# ABS_ENC_IF.net
KiCad netlist of a schematic drawn in Altium Designer
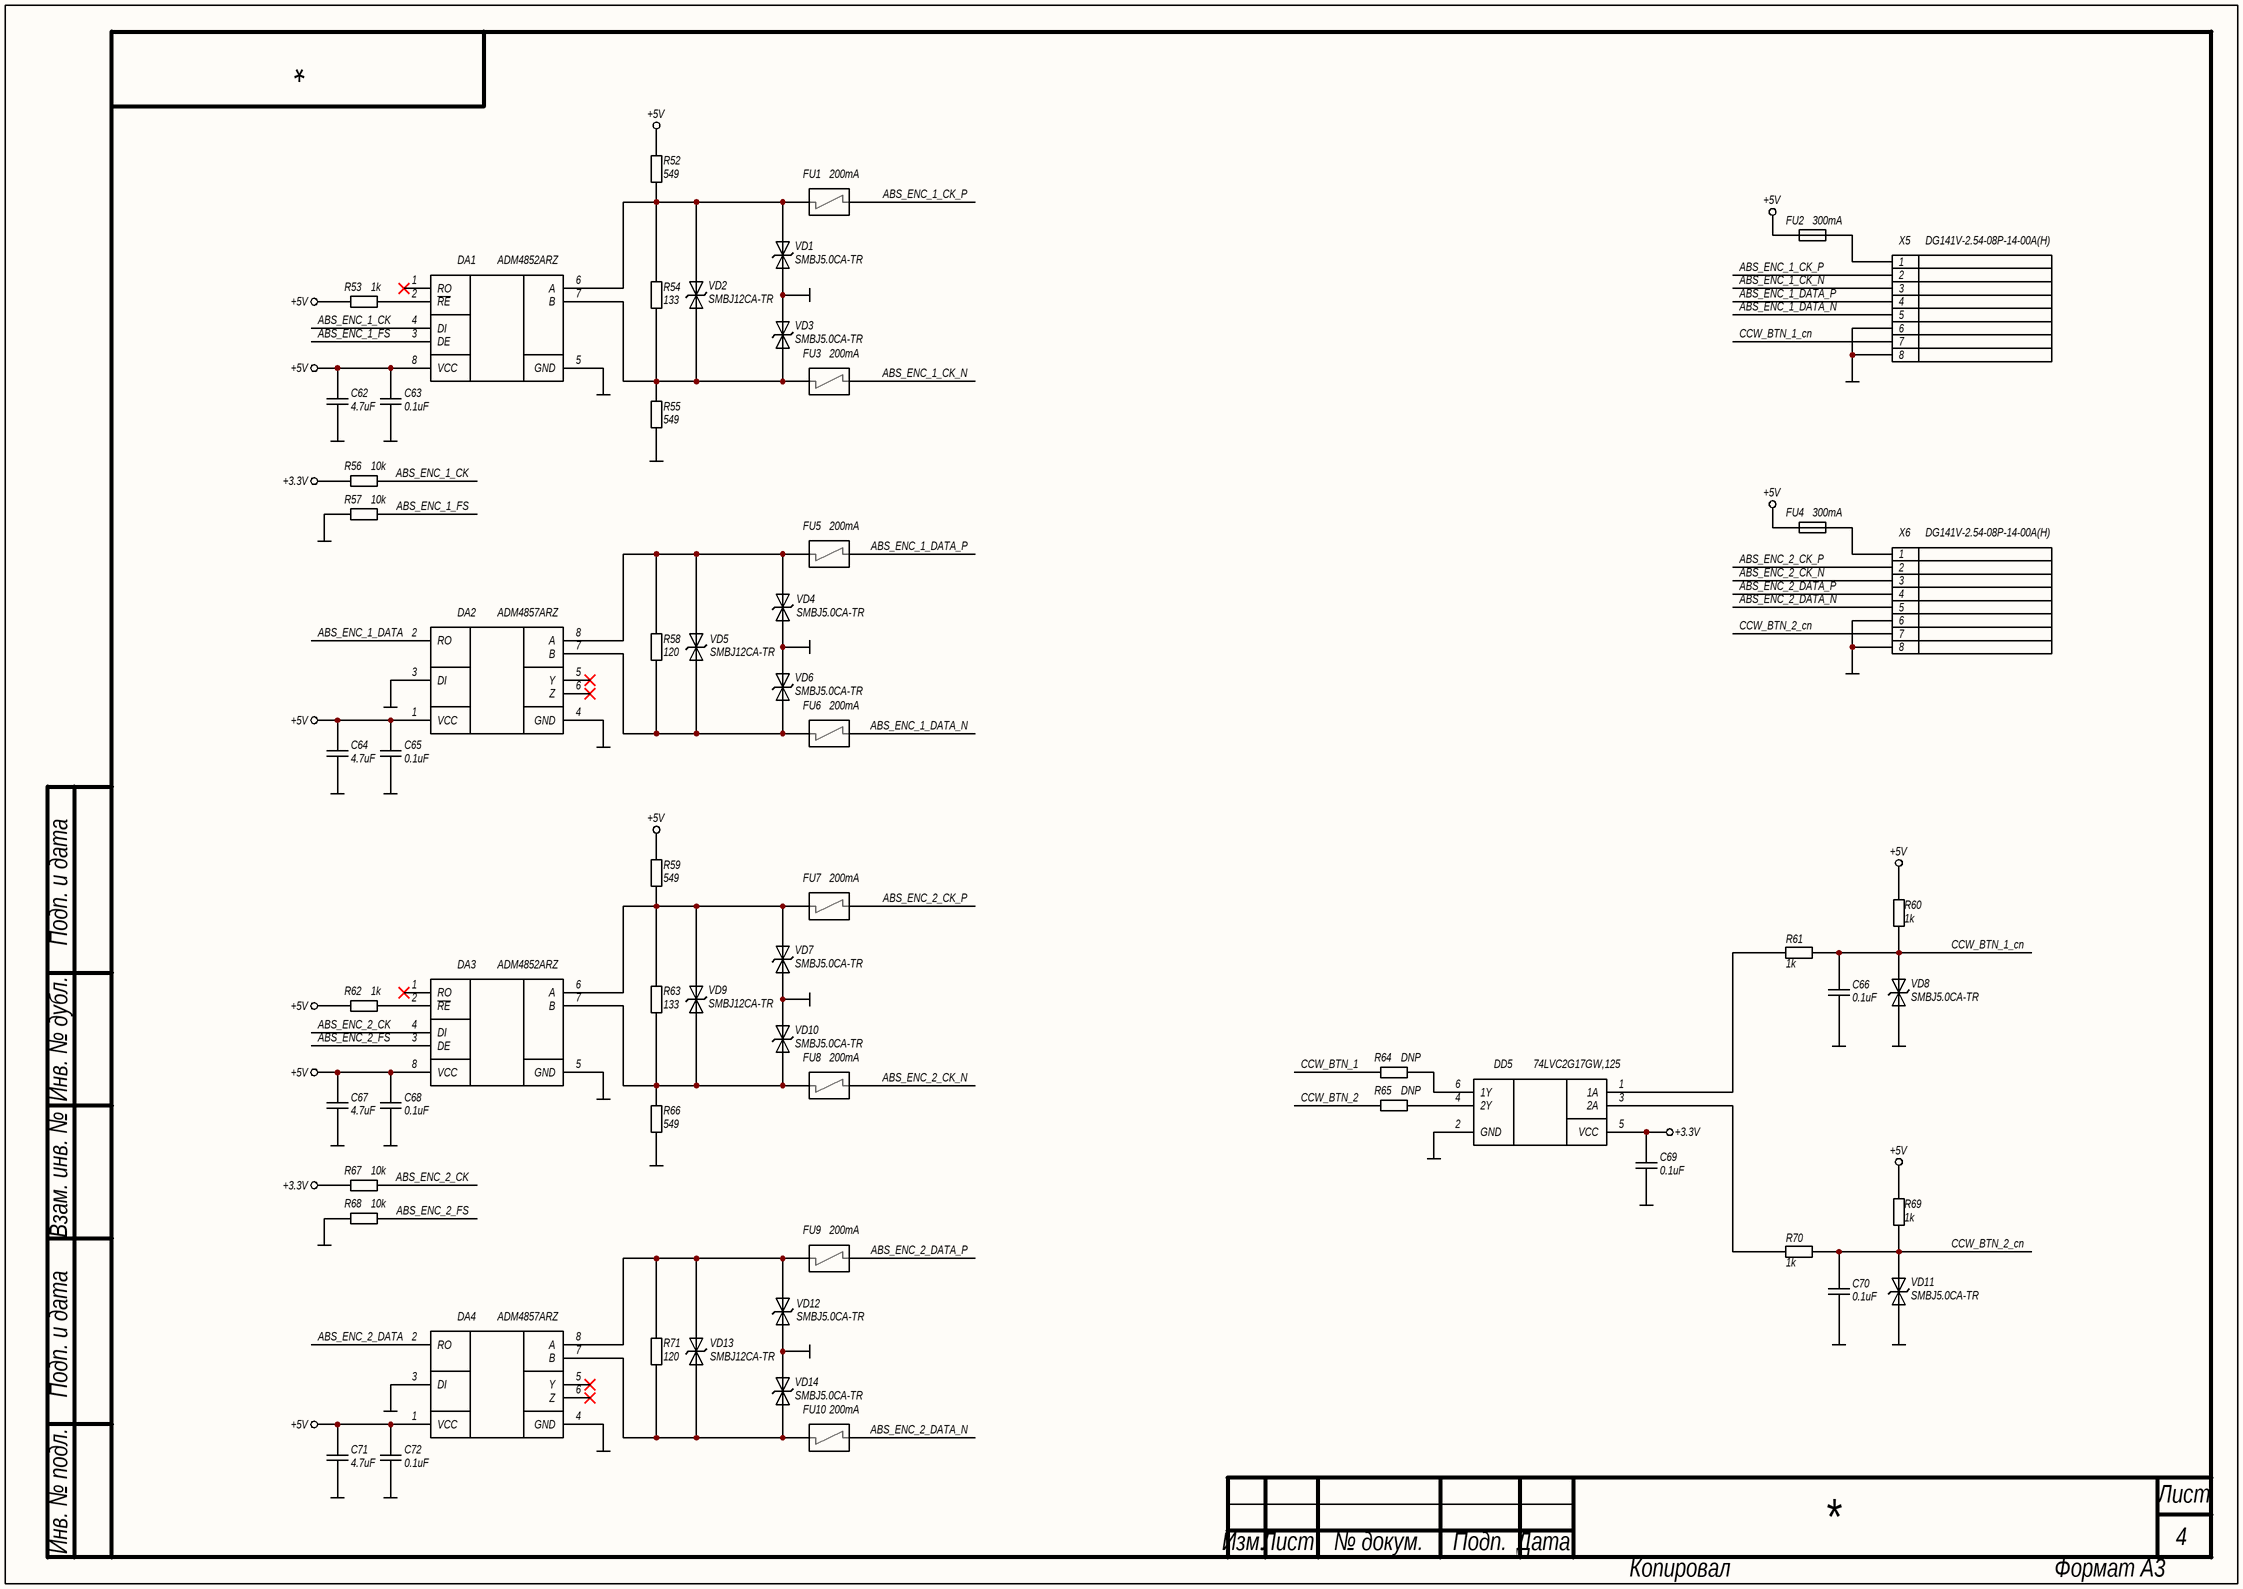
[diagram p0: ABS_ENC_IF.SchDoc]

(export (version "E")
  (design (tool "Eeschema 10.0.6"))
  (components
    (comp (ref "C62")
      (value "4.7uF")
      (footprint "C0603N")
      (description "Конденсатор")
      (libsource (lib "Components Library") (part "CAP_FIXED"))
    )
    (comp (ref "C63")
      (value "0.1uF")
      (footprint "C0603N")
      (description "Конденсатор")
      (libsource (lib "Components Library") (part "CAP_FIXED"))
    )
    (comp (ref "C64")
      (value "4.7uF")
      (footprint "C0603N")
      (description "Конденсатор")
      (libsource (lib "Components Library") (part "CAP_FIXED"))
    )
    (comp (ref "C65")
      (value "0.1uF")
      (footprint "C0603N")
      (description "Конденсатор")
      (libsource (lib "Components Library") (part "CAP_FIXED"))
    )
    (comp (ref "C66")
      (value "0.1uF")
      (footprint "C0603N")
      (description "Конденсатор")
      (libsource (lib "Components Library") (part "CAP_FIXED"))
    )
    (comp (ref "C67")
      (value "4.7uF")
      (footprint "C0603N")
      (description "Конденсатор")
      (libsource (lib "Components Library") (part "CAP_FIXED"))
    )
    (comp (ref "C68")
      (value "0.1uF")
      (footprint "C0603N")
      (description "Конденсатор")
      (libsource (lib "Components Library") (part "CAP_FIXED"))
    )
    (comp (ref "C69")
      (value "0.1uF")
      (footprint "C0603N")
      (description "Конденсатор")
      (libsource (lib "Components Library") (part "CAP_FIXED"))
    )
    (comp (ref "C70")
      (value "0.1uF")
      (footprint "C0603N")
      (description "Конденсатор")
      (libsource (lib "Components Library") (part "CAP_FIXED"))
    )
    (comp (ref "C71")
      (value "4.7uF")
      (footprint "C0603N")
      (description "Конденсатор")
      (libsource (lib "Components Library") (part "CAP_FIXED"))
    )
    (comp (ref "C72")
      (value "0.1uF")
      (footprint "C0603N")
      (description "Конденсатор")
      (libsource (lib "Components Library") (part "CAP_FIXED"))
    )
    (comp (ref "DA1")
      (value "ADM4852ARZ")
      (footprint "SOIC8")
      (description "Микросхема интерфейса RS485")
      (libsource (lib "Components Library") (part "ADM4852A"))
    )
    (comp (ref "DA2")
      (value "ADM4857ARZ")
      (footprint "SOIC8")
      (description "Микросхема интерфейса RS485")
      (libsource (lib "Components Library") (part "ADM4857A"))
    )
    (comp (ref "DA3")
      (value "ADM4852ARZ")
      (footprint "SOIC8")
      (description "Микросхема интерфейса RS485")
      (libsource (lib "Components Library") (part "ADM4852A"))
    )
    (comp (ref "DA4")
      (value "ADM4857ARZ")
      (footprint "SOIC8")
      (description "Микросхема интерфейса RS485")
      (libsource (lib "Components Library") (part "ADM4857A"))
    )
    (comp (ref "DD5")
      (value "74LVC2G17GW,125")
      (footprint "SOT363-2")
      (description "Микросхема сдвоенный триггер Шмитта")
      (libsource (lib "Components Library") (part "74LVC2G17"))
    )
    (comp (ref "FU1")
      (value "200mA")
      (footprint "TBU-CA")
      (description "Полупроводниковый предохранитель")
      (libsource (lib "Components Library") (part "FUSE_TBU"))
    )
    (comp (ref "FU2")
      (value "300mA")
      (footprint "MF-MSMF")
      (description "Плавкий предохранитель")
      (libsource (lib "Components Library") (part "FUSE"))
    )
    (comp (ref "FU3")
      (value "200mA")
      (footprint "TBU-CA")
      (description "Полупроводниковый предохранитель")
      (libsource (lib "Components Library") (part "FUSE_TBU"))
    )
    (comp (ref "FU4")
      (value "300mA")
      (footprint "MF-MSMF")
      (description "Плавкий предохранитель")
      (libsource (lib "Components Library") (part "FUSE"))
    )
    (comp (ref "FU5")
      (value "200mA")
      (footprint "TBU-CA")
      (description "Полупроводниковый предохранитель")
      (libsource (lib "Components Library") (part "FUSE_TBU"))
    )
    (comp (ref "FU6")
      (value "200mA")
      (footprint "TBU-CA")
      (description "Полупроводниковый предохранитель")
      (libsource (lib "Components Library") (part "FUSE_TBU"))
    )
    (comp (ref "FU7")
      (value "200mA")
      (footprint "TBU-CA")
      (description "Полупроводниковый предохранитель")
      (libsource (lib "Components Library") (part "FUSE_TBU"))
    )
    (comp (ref "FU8")
      (value "200mA")
      (footprint "TBU-CA")
      (description "Полупроводниковый предохранитель")
      (libsource (lib "Components Library") (part "FUSE_TBU"))
    )
    (comp (ref "FU9")
      (value "200mA")
      (footprint "TBU-CA")
      (description "Полупроводниковый предохранитель")
      (libsource (lib "Components Library") (part "FUSE_TBU"))
    )
    (comp (ref "FU10")
      (value "200mA")
      (footprint "TBU-CA")
      (description "Полупроводниковый предохранитель")
      (libsource (lib "Components Library") (part "FUSE_TBU"))
    )
    (comp (ref "R52")
      (value "549")
      (footprint "R0805N")
      (description "Резистор")
      (libsource (lib "") (part "RES_FIXED_2"))
    )
    (comp (ref "R53")
      (value "1k")
      (footprint "R0603N")
      (description "Резистор")
      (libsource (lib "") (part "RES_FIXED_1"))
    )
    (comp (ref "R54")
      (value "133")
      (footprint "R0805N")
      (description "Резистор")
      (libsource (lib "") (part "RES_FIXED_2"))
    )
    (comp (ref "R55")
      (value "549")
      (footprint "R0805N")
      (description "Резистор")
      (libsource (lib "") (part "RES_FIXED_2"))
    )
    (comp (ref "R56")
      (value "10k")
      (footprint "R0603N")
      (description "Резистор")
      (libsource (lib "") (part "RES_FIXED_1"))
    )
    (comp (ref "R57")
      (value "10k")
      (footprint "R0603N")
      (description "Резистор")
      (libsource (lib "") (part "RES_FIXED_1"))
    )
    (comp (ref "R58")
      (value "120")
      (footprint "R0805N")
      (description "Резистор")
      (libsource (lib "Components Library") (part "RES_FIXED"))
    )
    (comp (ref "R59")
      (value "549")
      (footprint "R0805N")
      (description "Резистор")
      (libsource (lib "") (part "RES_FIXED_2"))
    )
    (comp (ref "R60")
      (value "1k")
      (footprint "R0603N")
      (description "Резистор")
      (libsource (lib "Components Library") (part "RES_FIXED"))
    )
    (comp (ref "R61")
      (value "1k")
      (footprint "R0603N")
      (description "Резистор")
      (libsource (lib "") (part "RES_FIXED_3"))
    )
    (comp (ref "R62")
      (value "1k")
      (footprint "R0603N")
      (description "Резистор")
      (libsource (lib "") (part "RES_FIXED_1"))
    )
    (comp (ref "R63")
      (value "133")
      (footprint "R0805N")
      (description "Резистор")
      (libsource (lib "") (part "RES_FIXED_2"))
    )
    (comp (ref "R64")
      (value "DNP")
      (footprint "R0603N")
      (description "Резистор")
      (libsource (lib "") (part "RES_FIXED_1"))
    )
    (comp (ref "R65")
      (value "DNP")
      (footprint "R0603N")
      (description "Резистор")
      (libsource (lib "") (part "RES_FIXED_1"))
    )
    (comp (ref "R66")
      (value "549")
      (footprint "R0805N")
      (description "Резистор")
      (libsource (lib "") (part "RES_FIXED_2"))
    )
    (comp (ref "R67")
      (value "10k")
      (footprint "R0603N")
      (description "Резистор")
      (libsource (lib "") (part "RES_FIXED_1"))
    )
    (comp (ref "R68")
      (value "10k")
      (footprint "R0603N")
      (description "Резистор")
      (libsource (lib "") (part "RES_FIXED_1"))
    )
    (comp (ref "R69")
      (value "1k")
      (footprint "R0603N")
      (description "Резистор")
      (libsource (lib "Components Library") (part "RES_FIXED"))
    )
    (comp (ref "R70")
      (value "1k")
      (footprint "R0603N")
      (description "Резистор")
      (libsource (lib "") (part "RES_FIXED_3"))
    )
    (comp (ref "R71")
      (value "120")
      (footprint "R0805N")
      (description "Резистор")
      (libsource (lib "Components Library") (part "RES_FIXED"))
    )
    (comp (ref "VD1")
      (value "SMBJ5.0CA-TR")
      (footprint "SMB")
      (description "TVS диод двунаправленный")
      (libsource (lib "Components Library") (part "TVS_BIDIR"))
    )
    (comp (ref "VD2")
      (value "SMBJ12CA-TR")
      (footprint "SMB")
      (description "TVS диод двунаправленный")
      (libsource (lib "Components Library") (part "TVS_BIDIR"))
    )
    (comp (ref "VD3")
      (value "SMBJ5.0CA-TR")
      (footprint "SMB")
      (description "TVS диод двунаправленный")
      (libsource (lib "Components Library") (part "TVS_BIDIR"))
    )
    (comp (ref "VD4")
      (value "SMBJ5.0CA-TR")
      (footprint "SMB")
      (description "TVS диод двунаправленный")
      (libsource (lib "Components Library") (part "TVS_BIDIR"))
    )
    (comp (ref "VD5")
      (value "SMBJ12CA-TR")
      (footprint "SMB")
      (description "TVS диод двунаправленный")
      (libsource (lib "Components Library") (part "TVS_BIDIR"))
    )
    (comp (ref "VD6")
      (value "SMBJ5.0CA-TR")
      (footprint "SMB")
      (description "TVS диод двунаправленный")
      (libsource (lib "Components Library") (part "TVS_BIDIR"))
    )
    (comp (ref "VD7")
      (value "SMBJ5.0CA-TR")
      (footprint "SMB")
      (description "TVS диод двунаправленный")
      (libsource (lib "Components Library") (part "TVS_BIDIR"))
    )
    (comp (ref "VD8")
      (value "SMBJ5.0CA-TR")
      (footprint "SMB")
      (description "TVS диод двунаправленный")
      (libsource (lib "Components Library") (part "TVS_BIDIR"))
    )
    (comp (ref "VD9")
      (value "SMBJ12CA-TR")
      (footprint "SMB")
      (description "TVS диод двунаправленный")
      (libsource (lib "Components Library") (part "TVS_BIDIR"))
    )
    (comp (ref "VD10")
      (value "SMBJ5.0CA-TR")
      (footprint "SMB")
      (description "TVS диод двунаправленный")
      (libsource (lib "Components Library") (part "TVS_BIDIR"))
    )
    (comp (ref "VD11")
      (value "SMBJ5.0CA-TR")
      (footprint "SMB")
      (description "TVS диод двунаправленный")
      (libsource (lib "Components Library") (part "TVS_BIDIR"))
    )
    (comp (ref "VD12")
      (value "SMBJ5.0CA-TR")
      (footprint "SMB")
      (description "TVS диод двунаправленный")
      (libsource (lib "Components Library") (part "TVS_BIDIR"))
    )
    (comp (ref "VD13")
      (value "SMBJ12CA-TR")
      (footprint "SMB")
      (description "TVS диод двунаправленный")
      (libsource (lib "Components Library") (part "TVS_BIDIR"))
    )
    (comp (ref "VD14")
      (value "SMBJ5.0CA-TR")
      (footprint "SMB")
      (description "TVS диод двунаправленный")
      (libsource (lib "Components Library") (part "TVS_BIDIR"))
    )
    (comp (ref "X5")
      (value "DG141V-2.54-08P-14-00A(H)")
      (footprint "DG141V-2.54-08P-14-00A(H)")
      (description "Разъем, 8 контактов")
      (libsource (lib "Components Library") (part "Connector 8"))
    )
    (comp (ref "X6")
      (value "DG141V-2.54-08P-14-00A(H)")
      (footprint "DG141V-2.54-08P-14-00A(H)")
      (description "Разъем, 8 контактов")
      (libsource (lib "Components Library") (part "Connector 8"))
    )
  )
  (nets
    (net (code "1") (name "+3.3V") (class "Default")
      (node (ref "C69") (pin "2") (pinfunction "2_2") (pintype "passive"))
      (node (ref "DD5") (pin "5") (pinfunction "VCC_5") (pintype "power_in"))
      (node (ref "R56") (pin "2") (pinfunction "2_2") (pintype "passive"))
      (node (ref "R67") (pin "2") (pinfunction "2_2") (pintype "passive"))
    )
    (net (code "2") (name "+5V") (class "Default")
      (node (ref "C62") (pin "2") (pinfunction "2_2") (pintype "passive"))
      (node (ref "C63") (pin "2") (pinfunction "2_2") (pintype "passive"))
      (node (ref "C64") (pin "2") (pinfunction "2_2") (pintype "passive"))
      (node (ref "C65") (pin "2") (pinfunction "2_2") (pintype "passive"))
      (node (ref "C67") (pin "2") (pinfunction "2_2") (pintype "passive"))
      (node (ref "C68") (pin "2") (pinfunction "2_2") (pintype "passive"))
      (node (ref "C71") (pin "2") (pinfunction "2_2") (pintype "passive"))
      (node (ref "C72") (pin "2") (pinfunction "2_2") (pintype "passive"))
      (node (ref "DA1") (pin "8") (pinfunction "VCC_8") (pintype "power_in"))
      (node (ref "DA2") (pin "1") (pinfunction "VCC_1") (pintype "power_in"))
      (node (ref "DA3") (pin "8") (pinfunction "VCC_8") (pintype "power_in"))
      (node (ref "DA4") (pin "1") (pinfunction "VCC_1") (pintype "power_in"))
      (node (ref "FU2") (pin "1") (pinfunction "1_1") (pintype "passive"))
      (node (ref "FU4") (pin "1") (pinfunction "1_1") (pintype "passive"))
      (node (ref "R52") (pin "2") (pinfunction "2_2") (pintype "passive"))
      (node (ref "R53") (pin "2") (pinfunction "2_2") (pintype "passive"))
      (node (ref "R59") (pin "2") (pinfunction "2_2") (pintype "passive"))
      (node (ref "R60") (pin "1") (pinfunction "1_1") (pintype "passive"))
      (node (ref "R62") (pin "2") (pinfunction "2_2") (pintype "passive"))
      (node (ref "R69") (pin "1") (pinfunction "1_1") (pintype "passive"))
    )
    (net (code "3") (name "/ABS_ENC_1_CK") (class "Default")
      (node (ref "DA1") (pin "4") (pinfunction "DI_4") (pintype "power_in"))
      (node (ref "R56") (pin "1") (pinfunction "1_1") (pintype "passive"))
    )
    (net (code "4") (name "/ABS_ENC_1_CK_N") (class "Default")
      (node (ref "FU3") (pin "3") (pinfunction "IN/OUT_3") (pintype "passive"))
      (node (ref "X5") (pin "3") (pinfunction "3_3") (pintype "power_in"))
    )
    (net (code "5") (name "/ABS_ENC_1_CK_P") (class "Default")
      (node (ref "FU1") (pin "3") (pinfunction "IN/OUT_3") (pintype "passive"))
      (node (ref "X5") (pin "2") (pinfunction "2_2") (pintype "power_in"))
    )
    (net (code "6") (name "/ABS_ENC_1_DATA") (class "Default")
      (node (ref "DA2") (pin "2") (pinfunction "RO_2") (pintype "power_in"))
    )
    (net (code "7") (name "/ABS_ENC_1_DATA_N") (class "Default")
      (node (ref "FU6") (pin "3") (pinfunction "IN/OUT_3") (pintype "passive"))
      (node (ref "X5") (pin "5") (pinfunction "5_5") (pintype "power_in"))
    )
    (net (code "8") (name "/ABS_ENC_1_DATA_P") (class "Default")
      (node (ref "FU5") (pin "3") (pinfunction "IN/OUT_3") (pintype "passive"))
      (node (ref "X5") (pin "4") (pinfunction "4_4") (pintype "power_in"))
    )
    (net (code "9") (name "/ABS_ENC_1_FS") (class "Default")
      (node (ref "DA1") (pin "3") (pinfunction "DE_3") (pintype "power_in"))
      (node (ref "R57") (pin "1") (pinfunction "1_1") (pintype "passive"))
    )
    (net (code "10") (name "/ABS_ENC_2_CK") (class "Default")
      (node (ref "DA3") (pin "4") (pinfunction "DI_4") (pintype "power_in"))
      (node (ref "R67") (pin "1") (pinfunction "1_1") (pintype "passive"))
    )
    (net (code "11") (name "/ABS_ENC_2_CK_N") (class "Default")
      (node (ref "FU8") (pin "3") (pinfunction "IN/OUT_3") (pintype "passive"))
      (node (ref "X6") (pin "3") (pinfunction "3_3") (pintype "power_in"))
    )
    (net (code "12") (name "/ABS_ENC_2_CK_P") (class "Default")
      (node (ref "FU7") (pin "3") (pinfunction "IN/OUT_3") (pintype "passive"))
      (node (ref "X6") (pin "2") (pinfunction "2_2") (pintype "power_in"))
    )
    (net (code "13") (name "/ABS_ENC_2_DATA") (class "Default")
      (node (ref "DA4") (pin "2") (pinfunction "RO_2") (pintype "power_in"))
    )
    (net (code "14") (name "/ABS_ENC_2_DATA_N") (class "Default")
      (node (ref "FU10") (pin "3") (pinfunction "IN/OUT_3") (pintype "passive"))
      (node (ref "X6") (pin "5") (pinfunction "5_5") (pintype "power_in"))
    )
    (net (code "15") (name "/ABS_ENC_2_DATA_P") (class "Default")
      (node (ref "FU9") (pin "3") (pinfunction "IN/OUT_3") (pintype "passive"))
      (node (ref "X6") (pin "4") (pinfunction "4_4") (pintype "power_in"))
    )
    (net (code "16") (name "/ABS_ENC_2_FS") (class "Default")
      (node (ref "DA3") (pin "3") (pinfunction "DE_3") (pintype "power_in"))
      (node (ref "R68") (pin "1") (pinfunction "1_1") (pintype "passive"))
    )
    (net (code "17") (name "/CCW_BTN_1") (class "Default")
      (node (ref "R64") (pin "2") (pinfunction "2_2") (pintype "passive"))
    )
    (net (code "18") (name "/CCW_BTN_1_cn") (class "Default")
      (node (ref "C66") (pin "2") (pinfunction "2_2") (pintype "passive"))
      (node (ref "R60") (pin "2") (pinfunction "2_2") (pintype "passive"))
      (node (ref "R61") (pin "2") (pinfunction "2_2") (pintype "passive"))
      (node (ref "VD8") (pin "1") (pinfunction "A1_1") (pintype "passive"))
      (node (ref "X5") (pin "7") (pinfunction "7_7") (pintype "power_in"))
    )
    (net (code "19") (name "/CCW_BTN_2") (class "Default")
      (node (ref "R65") (pin "2") (pinfunction "2_2") (pintype "passive"))
    )
    (net (code "20") (name "/CCW_BTN_2_cn") (class "Default")
      (node (ref "C70") (pin "2") (pinfunction "2_2") (pintype "passive"))
      (node (ref "R69") (pin "2") (pinfunction "2_2") (pintype "passive"))
      (node (ref "R70") (pin "2") (pinfunction "2_2") (pintype "passive"))
      (node (ref "VD11") (pin "1") (pinfunction "A1_1") (pintype "passive"))
      (node (ref "X6") (pin "7") (pinfunction "7_7") (pintype "power_in"))
    )
    (net (code "21") (name "GND") (class "Default")
      (node (ref "C62") (pin "1") (pinfunction "1_1") (pintype "passive"))
      (node (ref "C63") (pin "1") (pinfunction "1_1") (pintype "passive"))
      (node (ref "C64") (pin "1") (pinfunction "1_1") (pintype "passive"))
      (node (ref "C65") (pin "1") (pinfunction "1_1") (pintype "passive"))
      (node (ref "C66") (pin "1") (pinfunction "1_1") (pintype "passive"))
      (node (ref "C67") (pin "1") (pinfunction "1_1") (pintype "passive"))
      (node (ref "C68") (pin "1") (pinfunction "1_1") (pintype "passive"))
      (node (ref "C69") (pin "1") (pinfunction "1_1") (pintype "passive"))
      (node (ref "C70") (pin "1") (pinfunction "1_1") (pintype "passive"))
      (node (ref "C71") (pin "1") (pinfunction "1_1") (pintype "passive"))
      (node (ref "C72") (pin "1") (pinfunction "1_1") (pintype "passive"))
      (node (ref "DA1") (pin "5") (pinfunction "GND_5") (pintype "power_in"))
      (node (ref "DA2") (pin "3") (pinfunction "DI_3") (pintype "power_in"))
      (node (ref "DA2") (pin "4") (pinfunction "GND_4") (pintype "power_in"))
      (node (ref "DA3") (pin "5") (pinfunction "GND_5") (pintype "power_in"))
      (node (ref "DA4") (pin "3") (pinfunction "DI_3") (pintype "power_in"))
      (node (ref "DA4") (pin "4") (pinfunction "GND_4") (pintype "power_in"))
      (node (ref "DD5") (pin "2") (pinfunction "GND_2") (pintype "power_in"))
      (node (ref "R55") (pin "1") (pinfunction "1_1") (pintype "passive"))
      (node (ref "R57") (pin "2") (pinfunction "2_2") (pintype "passive"))
      (node (ref "R66") (pin "1") (pinfunction "1_1") (pintype "passive"))
      (node (ref "R68") (pin "2") (pinfunction "2_2") (pintype "passive"))
      (node (ref "VD1") (pin "2") (pinfunction "A2_2") (pintype "passive"))
      (node (ref "VD10") (pin "2") (pinfunction "A2_2") (pintype "passive"))
      (node (ref "VD11") (pin "2") (pinfunction "A2_2") (pintype "passive"))
      (node (ref "VD12") (pin "2") (pinfunction "A2_2") (pintype "passive"))
      (node (ref "VD14") (pin "2") (pinfunction "A2_2") (pintype "passive"))
      (node (ref "VD3") (pin "2") (pinfunction "A2_2") (pintype "passive"))
      (node (ref "VD4") (pin "2") (pinfunction "A2_2") (pintype "passive"))
      (node (ref "VD6") (pin "2") (pinfunction "A2_2") (pintype "passive"))
      (node (ref "VD7") (pin "2") (pinfunction "A2_2") (pintype "passive"))
      (node (ref "VD8") (pin "2") (pinfunction "A2_2") (pintype "passive"))
      (node (ref "X5") (pin "6") (pinfunction "6_6") (pintype "power_in"))
      (node (ref "X5") (pin "8") (pinfunction "8_8") (pintype "power_in"))
      (node (ref "X6") (pin "6") (pinfunction "6_6") (pintype "power_in"))
      (node (ref "X6") (pin "8") (pinfunction "8_8") (pintype "power_in"))
    )
    (net (code "22") (name "Net-(DA1-A)") (class "Default")
      (node (ref "DA1") (pin "6") (pinfunction "A_6") (pintype "power_in"))
      (node (ref "FU1") (pin "1") (pinfunction "IN/OUT_1") (pintype "passive"))
      (node (ref "R52") (pin "1") (pinfunction "1_1") (pintype "passive"))
      (node (ref "R54") (pin "2") (pinfunction "2_2") (pintype "passive"))
      (node (ref "VD1") (pin "1") (pinfunction "A1_1") (pintype "passive"))
      (node (ref "VD2") (pin "1") (pinfunction "A1_1") (pintype "passive"))
    )
    (net (code "23") (name "Net-(DA1-B)") (class "Default")
      (node (ref "DA1") (pin "7") (pinfunction "B_7") (pintype "power_in"))
      (node (ref "FU3") (pin "1") (pinfunction "IN/OUT_1") (pintype "passive"))
      (node (ref "R54") (pin "1") (pinfunction "1_1") (pintype "passive"))
      (node (ref "R55") (pin "2") (pinfunction "2_2") (pintype "passive"))
      (node (ref "VD2") (pin "2") (pinfunction "A2_2") (pintype "passive"))
      (node (ref "VD3") (pin "1") (pinfunction "A1_1") (pintype "passive"))
    )
    (net (code "24") (name "Net-(DA1-~{RE})") (class "Default")
      (node (ref "DA1") (pin "2") (pinfunction "~{RE}_2") (pintype "power_in"))
      (node (ref "R53") (pin "1") (pinfunction "1_1") (pintype "passive"))
    )
    (net (code "25") (name "Net-(DA2-A)") (class "Default")
      (node (ref "DA2") (pin "8") (pinfunction "A_8") (pintype "power_in"))
      (node (ref "FU5") (pin "1") (pinfunction "IN/OUT_1") (pintype "passive"))
      (node (ref "R58") (pin "1") (pinfunction "1_1") (pintype "passive"))
      (node (ref "VD4") (pin "1") (pinfunction "A1_1") (pintype "passive"))
      (node (ref "VD5") (pin "1") (pinfunction "A1_1") (pintype "passive"))
    )
    (net (code "26") (name "Net-(DA2-B)") (class "Default")
      (node (ref "DA2") (pin "7") (pinfunction "B_7") (pintype "power_in"))
      (node (ref "FU6") (pin "1") (pinfunction "IN/OUT_1") (pintype "passive"))
      (node (ref "R58") (pin "2") (pinfunction "2_2") (pintype "passive"))
      (node (ref "VD5") (pin "2") (pinfunction "A2_2") (pintype "passive"))
      (node (ref "VD6") (pin "1") (pinfunction "A1_1") (pintype "passive"))
    )
    (net (code "27") (name "Net-(DA3-A)") (class "Default")
      (node (ref "DA3") (pin "6") (pinfunction "A_6") (pintype "power_in"))
      (node (ref "FU7") (pin "1") (pinfunction "IN/OUT_1") (pintype "passive"))
      (node (ref "R59") (pin "1") (pinfunction "1_1") (pintype "passive"))
      (node (ref "R63") (pin "2") (pinfunction "2_2") (pintype "passive"))
      (node (ref "VD7") (pin "1") (pinfunction "A1_1") (pintype "passive"))
      (node (ref "VD9") (pin "1") (pinfunction "A1_1") (pintype "passive"))
    )
    (net (code "28") (name "Net-(DA3-B)") (class "Default")
      (node (ref "DA3") (pin "7") (pinfunction "B_7") (pintype "power_in"))
      (node (ref "FU8") (pin "1") (pinfunction "IN/OUT_1") (pintype "passive"))
      (node (ref "R63") (pin "1") (pinfunction "1_1") (pintype "passive"))
      (node (ref "R66") (pin "2") (pinfunction "2_2") (pintype "passive"))
      (node (ref "VD10") (pin "1") (pinfunction "A1_1") (pintype "passive"))
      (node (ref "VD9") (pin "2") (pinfunction "A2_2") (pintype "passive"))
    )
    (net (code "29") (name "Net-(DA3-~{RE})") (class "Default")
      (node (ref "DA3") (pin "2") (pinfunction "~{RE}_2") (pintype "power_in"))
      (node (ref "R62") (pin "1") (pinfunction "1_1") (pintype "passive"))
    )
    (net (code "30") (name "Net-(DA4-A)") (class "Default")
      (node (ref "DA4") (pin "8") (pinfunction "A_8") (pintype "power_in"))
      (node (ref "FU9") (pin "1") (pinfunction "IN/OUT_1") (pintype "passive"))
      (node (ref "R71") (pin "1") (pinfunction "1_1") (pintype "passive"))
      (node (ref "VD12") (pin "1") (pinfunction "A1_1") (pintype "passive"))
      (node (ref "VD13") (pin "1") (pinfunction "A1_1") (pintype "passive"))
    )
    (net (code "31") (name "Net-(DA4-B)") (class "Default")
      (node (ref "DA4") (pin "7") (pinfunction "B_7") (pintype "power_in"))
      (node (ref "FU10") (pin "1") (pinfunction "IN/OUT_1") (pintype "passive"))
      (node (ref "R71") (pin "2") (pinfunction "2_2") (pintype "passive"))
      (node (ref "VD13") (pin "2") (pinfunction "A2_2") (pintype "passive"))
      (node (ref "VD14") (pin "1") (pinfunction "A1_1") (pintype "passive"))
    )
    (net (code "32") (name "Net-(DD5-1A)") (class "Default")
      (node (ref "DD5") (pin "1") (pinfunction "1A_1") (pintype "power_in"))
      (node (ref "R61") (pin "1") (pinfunction "1_1") (pintype "passive"))
    )
    (net (code "33") (name "Net-(DD5-1Y)") (class "Default")
      (node (ref "DD5") (pin "6") (pinfunction "1Y_6") (pintype "power_in"))
      (node (ref "R64") (pin "1") (pinfunction "1_1") (pintype "passive"))
    )
    (net (code "34") (name "Net-(DD5-2A)") (class "Default")
      (node (ref "DD5") (pin "3") (pinfunction "2A_3") (pintype "power_in"))
      (node (ref "R70") (pin "1") (pinfunction "1_1") (pintype "passive"))
    )
    (net (code "35") (name "Net-(DD5-2Y)") (class "Default")
      (node (ref "DD5") (pin "4") (pinfunction "2Y_4") (pintype "power_in"))
      (node (ref "R65") (pin "1") (pinfunction "1_1") (pintype "passive"))
    )
    (net (code "36") (name "Net-(FU2-Pad2)") (class "Default")
      (node (ref "FU2") (pin "2") (pinfunction "2_2") (pintype "passive"))
      (node (ref "X5") (pin "1") (pinfunction "1_1") (pintype "power_in"))
    )
    (net (code "37") (name "Net-(FU4-Pad2)") (class "Default")
      (node (ref "FU4") (pin "2") (pinfunction "2_2") (pintype "passive"))
      (node (ref "X6") (pin "1") (pinfunction "1_1") (pintype "power_in"))
    )
    (net (code "38") (name "unconnected-(DA1-RO-Pad1)") (class "Default")
      (node (ref "DA1") (pin "1") (pinfunction "RO_1") (pintype "power_in+no_connect"))
    )
    (net (code "39") (name "unconnected-(DA2-Y-Pad5)") (class "Default")
      (node (ref "DA2") (pin "5") (pinfunction "Y_5") (pintype "power_in+no_connect"))
    )
    (net (code "40") (name "unconnected-(DA2-Z-Pad6)") (class "Default")
      (node (ref "DA2") (pin "6") (pinfunction "Z_6") (pintype "power_in+no_connect"))
    )
    (net (code "41") (name "unconnected-(DA3-RO-Pad1)") (class "Default")
      (node (ref "DA3") (pin "1") (pinfunction "RO_1") (pintype "power_in+no_connect"))
    )
    (net (code "42") (name "unconnected-(DA4-Y-Pad5)") (class "Default")
      (node (ref "DA4") (pin "5") (pinfunction "Y_5") (pintype "power_in+no_connect"))
    )
    (net (code "43") (name "unconnected-(DA4-Z-Pad6)") (class "Default")
      (node (ref "DA4") (pin "6") (pinfunction "Z_6") (pintype "power_in+no_connect"))
    )
  )
)
